# display.net
KiCad netlist of a schematic drawn in Altium Designer
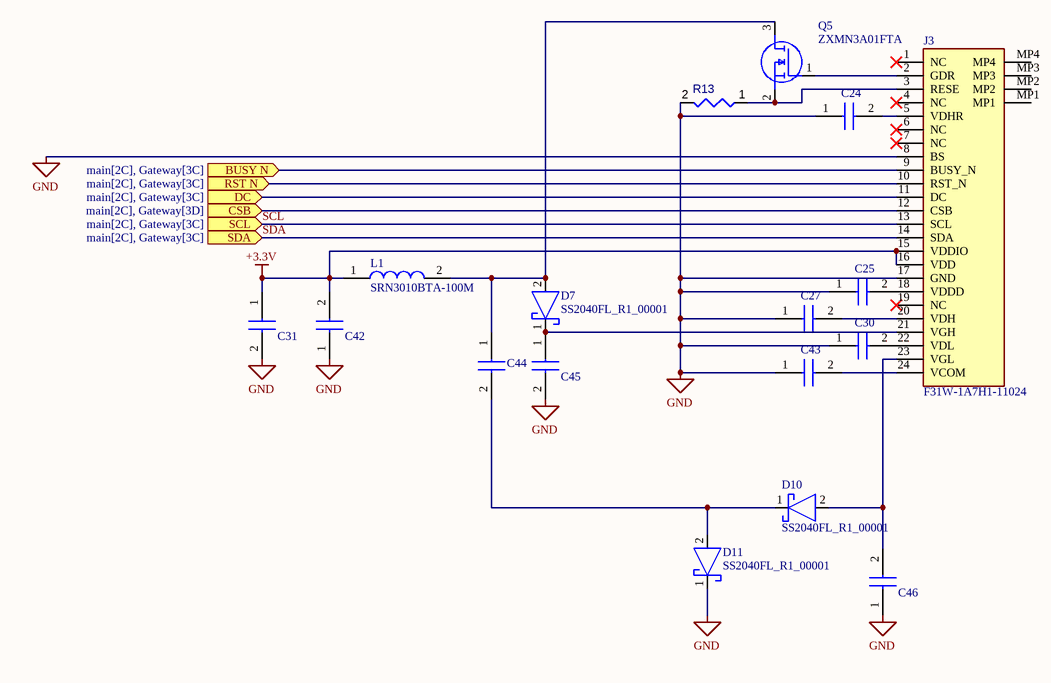
[diagram p0: display.SchDoc]

(export (version "E")
  (design (tool "Eeschema 10.0.6"))
  (components
    (comp (ref "C24")
      (value "CL21Y105KCYVPNE")
      (footprint "SamacSys:CAPC2012X145N")
      (description "Capacitor")
      (libsource (lib "SamacSys") (part "CL21Y105KCYVPNE"))
    )
    (comp (ref "C25")
      (value "CL21Y105KCYVPNE")
      (footprint "SamacSys:CAPC2012X145N")
      (description "Capacitor")
      (libsource (lib "SamacSys") (part "CL21Y105KCYVPNE"))
    )
    (comp (ref "C27")
      (value "CL21Y105KCYVPNE")
      (footprint "SamacSys:CAPC2012X145N")
      (description "Capacitor")
      (libsource (lib "SamacSys") (part "CL21Y105KCYVPNE"))
    )
    (comp (ref "C30")
      (value "CL21Y105KCYVPNE")
      (footprint "SamacSys:CAPC2012X145N")
      (description "Capacitor")
      (libsource (lib "SamacSys") (part "CL21Y105KCYVPNE"))
    )
    (comp (ref "C31")
      (value "C1005X5R1E104K050BC")
      (footprint "SamacSys:CAPC1005X55N")
      (description "Capacitor")
      (fields (field (name "MOUSER PART NUMBER") "810-C1005X5R1E104K"))
      (libsource (lib "*") (part "C1005X5R1E104K050BC"))
    )
    (comp (ref "C42")
      (value "CL21Y105KCYVPNE")
      (footprint "SamacSys:CAPC2012X145N")
      (description "Capacitor")
      (libsource (lib "SamacSys") (part "CL21Y105KCYVPNE"))
    )
    (comp (ref "C43")
      (value "CL21Y105KCYVPNE")
      (footprint "SamacSys:CAPC2012X145N")
      (description "Capacitor")
      (libsource (lib "SamacSys") (part "CL21Y105KCYVPNE"))
    )
    (comp (ref "C44")
      (value "KAM32LR72A475KU")
      (footprint "SamacSys:CAPC3225X94N")
      (description "Capacitor 4.7u")
      (fields (field (name "MOUSER PART NUMBER") "581-KAM32LR72A475KU"))
      (libsource (lib "*") (part "KAM32LR72A475KU"))
    )
    (comp (ref "C45")
      (value "CL21Y105KCYVPNE")
      (footprint "SamacSys:CAPC2012X145N")
      (description "Capacitor")
      (libsource (lib "SamacSys") (part "CL21Y105KCYVPNE"))
    )
    (comp (ref "C46")
      (value "CL21Y105KCYVPNE")
      (footprint "SamacSys:CAPC2012X145N")
      (description "Capacitor")
      (libsource (lib "SamacSys") (part "CL21Y105KCYVPNE"))
    )
    (comp (ref "D7")
      (value "SS2040FL_R1_00001")
      (footprint "SamacSys:SODFL3618X110N")
      (description "Schottky Diode")
      (fields (field (name "MOUSER PART NUMBER") "241-SS2040FLR100001"))
      (libsource (lib "SamacSys") (part "SS2040FL_R1_00001"))
    )
    (comp (ref "D10")
      (value "SS2040FL_R1_00001")
      (footprint "SamacSys:SODFL3618X110N")
      (description "Schottky Diode")
      (fields (field (name "MOUSER PART NUMBER") "241-SS2040FLR100001"))
      (libsource (lib "SamacSys") (part "SS2040FL_R1_00001"))
    )
    (comp (ref "D11")
      (value "SS2040FL_R1_00001")
      (footprint "SamacSys:SODFL3618X110N")
      (description "Schottky Diode")
      (fields (field (name "MOUSER PART NUMBER") "241-SS2040FLR100001"))
      (libsource (lib "SamacSys") (part "SS2040FL_R1_00001"))
    )
    (comp (ref "J3")
      (value "F31W-1A7H1-11024")
      (footprint "SamacSys:F31W1A7H111024")
      (description "Connector")
      (fields (field (name "MOUSER PART NUMBER") "649-F31W-1A7H1-11024"))
      (libsource (lib "SamacSys") (part "F31W-1A7H1-11024"))
    )
    (comp (ref "L1")
      (value "SRN3010BTA-100M")
      (footprint "SamacSys:SRN3010BTA100M")
      (description "Inductor")
      (fields (field (name "MOUSER PART NUMBER") "652-SRN3010BTA-100M"))
      (libsource (lib "SamacSys") (part "SRN3010BTA-100M"))
    )
    (comp (ref "Q5")
      (value "ZXMN3A01FTA")
      (footprint "SamacSys:SOT96P240X110-3N")
      (description "MOSFET (N-Channel)")
      (fields (field (name "MOUSER PART NUMBER") "522-ZXMN3A01FTA"))
      (libsource (lib "*") (part "ZXMN3A01FTA"))
    )
    (comp (ref "R13")
      (value "PE1206FRF070R47L")
      (footprint "PE1206FRF070R47L-Footprint-1")
      (libsource (lib "marina santos") (part "RES-2"))
    )
  )
  (nets
    (net (code "1") (name "+3.3V") (class "Default")
      (node (ref "C31") (pin "1") (pinfunction "1_1") (pintype "passive"))
      (node (ref "C42") (pin "2") (pinfunction "2_2") (pintype "passive"))
      (node (ref "J3") (pin "15") (pinfunction "VDDIO_15") (pintype "passive"))
      (node (ref "J3") (pin "16") (pinfunction "VDD_16") (pintype "passive"))
      (node (ref "L1") (pin "1") (pinfunction "1_1") (pintype "passive"))
    )
    (net (code "2") (name "/BUSY N") (class "Default")
      (node (ref "J3") (pin "9") (pinfunction "BUSY_N_9") (pintype "passive"))
    )
    (net (code "3") (name "/CSB") (class "Default")
      (node (ref "J3") (pin "12") (pinfunction "CSB_12") (pintype "passive"))
    )
    (net (code "4") (name "/DC") (class "Default")
      (node (ref "J3") (pin "11") (pinfunction "DC_11") (pintype "passive"))
    )
    (net (code "5") (name "/RST N") (class "Default")
      (node (ref "J3") (pin "10") (pinfunction "RST_N_10") (pintype "passive"))
    )
    (net (code "6") (name "/SCL") (class "Default")
      (node (ref "J3") (pin "13") (pinfunction "SCL_13") (pintype "passive"))
    )
    (net (code "7") (name "/SDA") (class "Default")
      (node (ref "J3") (pin "14") (pinfunction "SDA_14") (pintype "passive"))
    )
    (net (code "8") (name "GND") (class "Default")
      (node (ref "C24") (pin "1") (pinfunction "1_1") (pintype "passive"))
      (node (ref "C25") (pin "1") (pinfunction "1_1") (pintype "passive"))
      (node (ref "C27") (pin "1") (pinfunction "1_1") (pintype "passive"))
      (node (ref "C30") (pin "1") (pinfunction "1_1") (pintype "passive"))
      (node (ref "C31") (pin "2") (pinfunction "2_2") (pintype "passive"))
      (node (ref "C42") (pin "1") (pinfunction "1_1") (pintype "passive"))
      (node (ref "C43") (pin "1") (pinfunction "1_1") (pintype "passive"))
      (node (ref "C45") (pin "2") (pinfunction "2_2") (pintype "passive"))
      (node (ref "C46") (pin "1") (pinfunction "1_1") (pintype "passive"))
      (node (ref "D11") (pin "1") (pinfunction "K_1") (pintype "passive"))
      (node (ref "J3") (pin "17") (pinfunction "GND_17") (pintype "passive"))
      (node (ref "J3") (pin "8") (pinfunction "BS_8") (pintype "passive"))
      (node (ref "R13") (pin "2") (pinfunction "2_2") (pintype "passive"))
    )
    (net (code "9") (name "Net-(D7-A)") (class "Default")
      (node (ref "C44") (pin "1") (pinfunction "1_1") (pintype "passive"))
      (node (ref "D7") (pin "2") (pinfunction "A_2") (pintype "passive"))
      (node (ref "L1") (pin "2") (pinfunction "2_2") (pintype "passive"))
      (node (ref "Q5") (pin "3") (pinfunction "D_3") (pintype "passive"))
    )
    (net (code "10") (name "Net-(D7-K)") (class "Default")
      (node (ref "C45") (pin "1") (pinfunction "1_1") (pintype "passive"))
      (node (ref "D7") (pin "1") (pinfunction "K_1") (pintype "passive"))
      (node (ref "J3") (pin "21") (pinfunction "VGH_21") (pintype "passive"))
    )
    (net (code "11") (name "Net-(D10-A)") (class "Default")
      (node (ref "C46") (pin "2") (pinfunction "2_2") (pintype "passive"))
      (node (ref "D10") (pin "2") (pinfunction "A_2") (pintype "passive"))
      (node (ref "J3") (pin "23") (pinfunction "VGL_23") (pintype "passive"))
    )
    (net (code "12") (name "Net-(D10-K)") (class "Default")
      (node (ref "C44") (pin "2") (pinfunction "2_2") (pintype "passive"))
      (node (ref "D10") (pin "1") (pinfunction "K_1") (pintype "passive"))
      (node (ref "D11") (pin "2") (pinfunction "A_2") (pintype "passive"))
    )
    (net (code "13") (name "Net-(J3-GDR)") (class "Default")
      (node (ref "J3") (pin "2") (pinfunction "GDR_2") (pintype "passive"))
      (node (ref "Q5") (pin "1") (pinfunction "G_1") (pintype "passive"))
    )
    (net (code "14") (name "Net-(J3-RESE)") (class "Default")
      (node (ref "J3") (pin "3") (pinfunction "RESE_3") (pintype "passive"))
      (node (ref "Q5") (pin "2") (pinfunction "S_2") (pintype "passive"))
      (node (ref "R13") (pin "1") (pinfunction "1_1") (pintype "passive"))
    )
    (net (code "15") (name "Net-(J3-VCOM)") (class "Default")
      (node (ref "C43") (pin "2") (pinfunction "2_2") (pintype "passive"))
      (node (ref "J3") (pin "24") (pinfunction "VCOM_24") (pintype "passive"))
    )
    (net (code "16") (name "Net-(J3-VDDD)") (class "Default")
      (node (ref "C25") (pin "2") (pinfunction "2_2") (pintype "passive"))
      (node (ref "J3") (pin "18") (pinfunction "VDDD_18") (pintype "passive"))
    )
    (net (code "17") (name "Net-(J3-VDH)") (class "Default")
      (node (ref "C27") (pin "2") (pinfunction "2_2") (pintype "passive"))
      (node (ref "J3") (pin "20") (pinfunction "VDH_20") (pintype "passive"))
    )
    (net (code "18") (name "Net-(J3-VDHR)") (class "Default")
      (node (ref "C24") (pin "2") (pinfunction "2_2") (pintype "passive"))
      (node (ref "J3") (pin "5") (pinfunction "VDHR_5") (pintype "passive"))
    )
    (net (code "19") (name "Net-(J3-VDL)") (class "Default")
      (node (ref "C30") (pin "2") (pinfunction "2_2") (pintype "passive"))
      (node (ref "J3") (pin "22") (pinfunction "VDL_22") (pintype "passive"))
    )
    (net (code "20") (name "unconnected-(J3-NC-Pad1)") (class "Default")
      (node (ref "J3") (pin "1") (pinfunction "NC_1") (pintype "passive+no_connect"))
    )
    (net (code "21") (name "unconnected-(J3-NC-Pad4)") (class "Default")
      (node (ref "J3") (pin "4") (pinfunction "NC_4") (pintype "passive+no_connect"))
    )
    (net (code "22") (name "unconnected-(J3-NC-Pad6)") (class "Default")
      (node (ref "J3") (pin "6") (pinfunction "NC_6") (pintype "passive+no_connect"))
    )
    (net (code "23") (name "unconnected-(J3-NC-Pad7)") (class "Default")
      (node (ref "J3") (pin "7") (pinfunction "NC_7") (pintype "passive+no_connect"))
    )
    (net (code "24") (name "unconnected-(J3-NC-Pad19)") (class "Default")
      (node (ref "J3") (pin "19") (pinfunction "NC_19") (pintype "passive+no_connect"))
    )
    (net (code "25") (name "unconnected-(J3-PadMP1)") (class "Default")
      (node (ref "J3") (pin "MP1") (pinfunction "MP1_MP1") (pintype "passive"))
    )
    (net (code "26") (name "unconnected-(J3-PadMP2)") (class "Default")
      (node (ref "J3") (pin "MP2") (pinfunction "MP2_MP2") (pintype "passive"))
    )
    (net (code "27") (name "unconnected-(J3-PadMP3)") (class "Default")
      (node (ref "J3") (pin "MP3") (pinfunction "MP3_MP3") (pintype "passive"))
    )
    (net (code "28") (name "unconnected-(J3-PadMP4)") (class "Default")
      (node (ref "J3") (pin "MP4") (pinfunction "MP4_MP4") (pintype "passive"))
    )
  )
)
